# AmbaSat-1v1-01-NO-solar.net
KiCad netlist of a schematic drawn in EAGLE
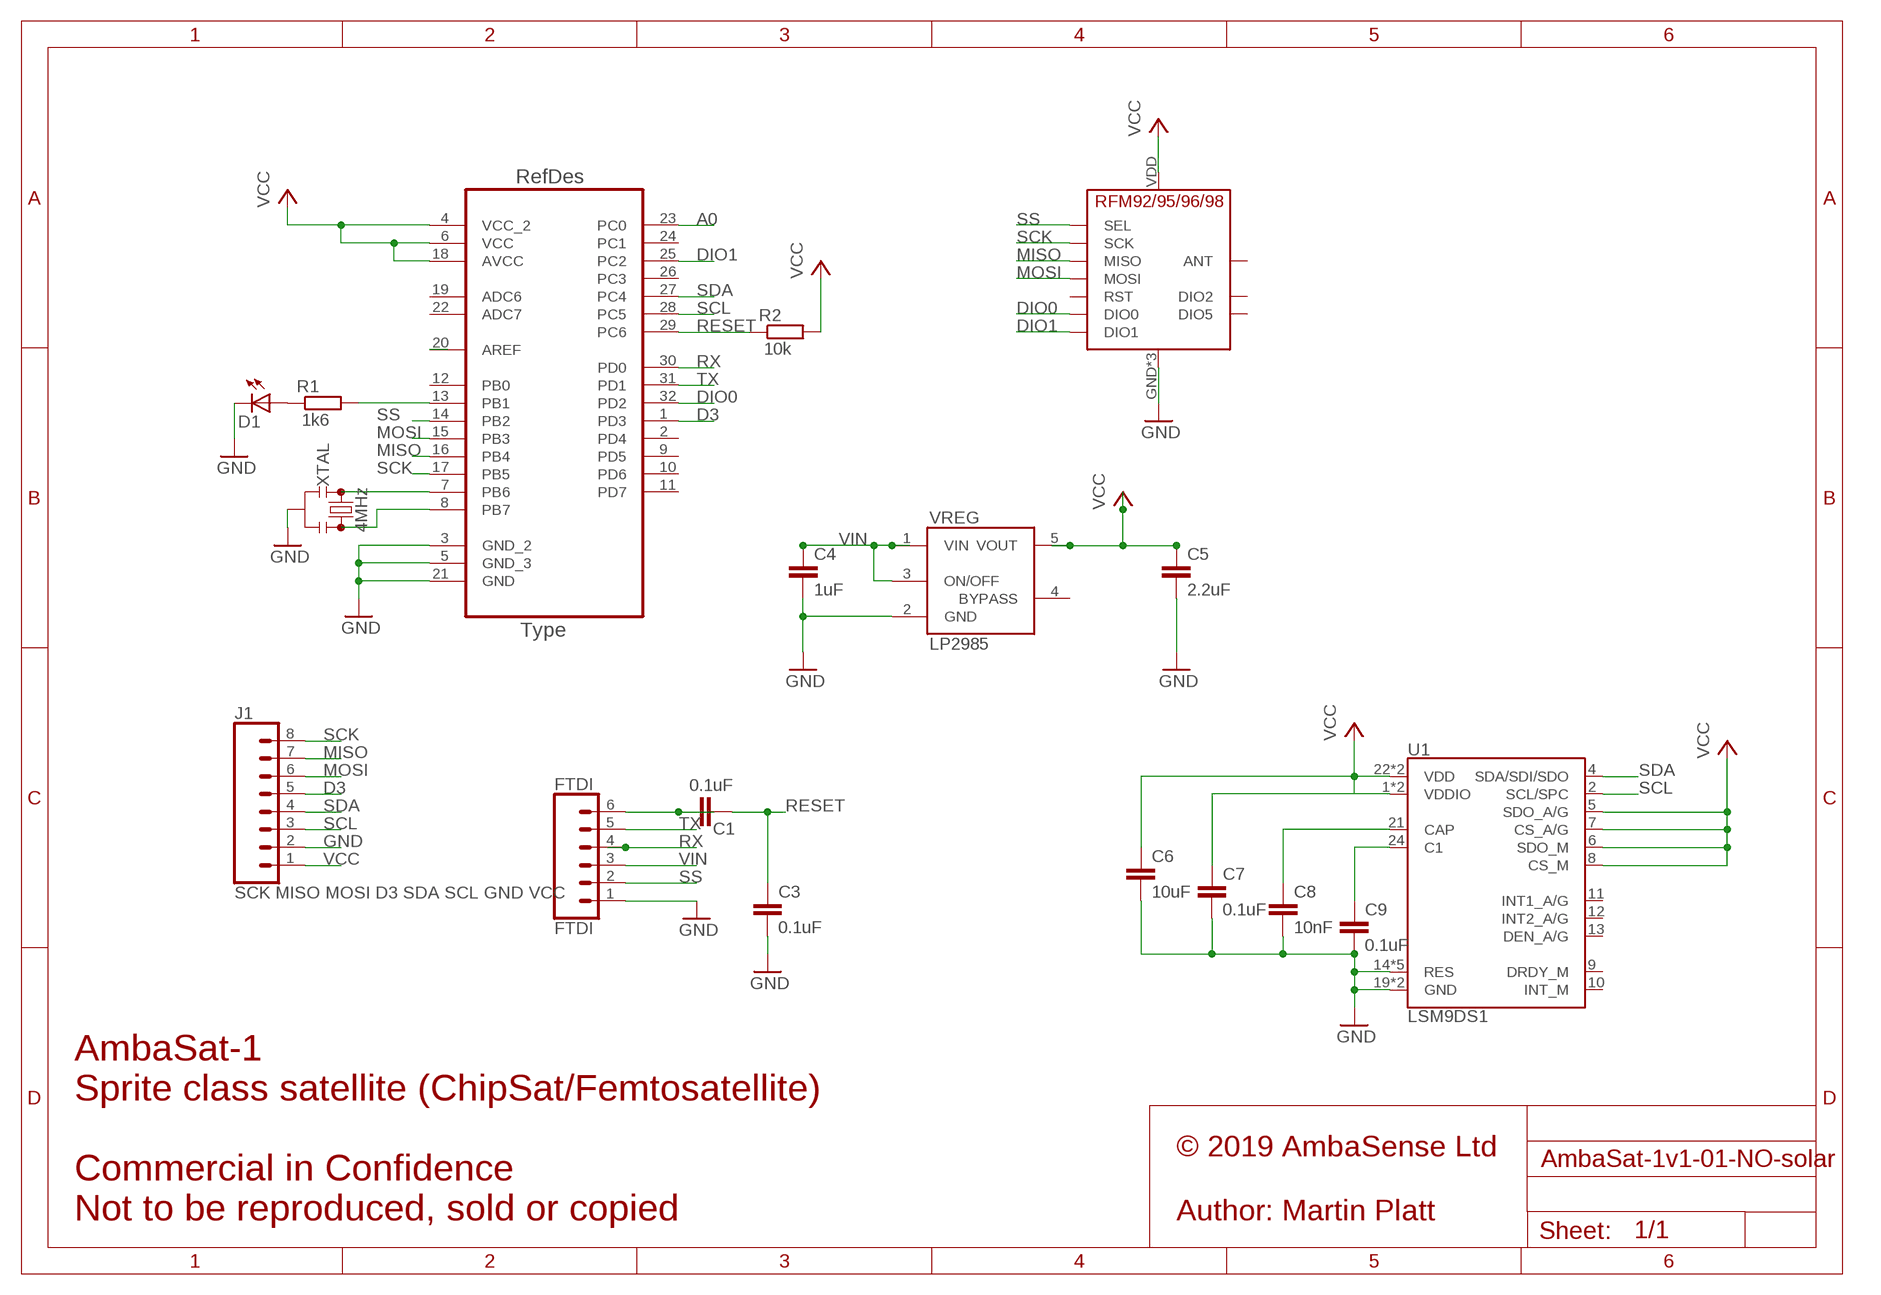
[diagram p0: schematic, sheet 1]

(export (version "E")
  (design (tool "Eeschema 10.0.6"))
  (components
    (comp (ref "ATMEGA328P-AU")
      (value "ATMEGA328P-AU")
      (footprint "eagle-import:QFP80P900X900X120-32N")
      (libsource (lib "eagle-import") (part "ATMEGA328P-AU"))
    )
    (comp (ref "C1")
      (value "0.1uF")
      (footprint "eagle-import:C0805K")
      (libsource (lib "eagle-import") (part "C-EUC0805K"))
    )
    (comp (ref "C3")
      (value "0.1uF")
      (footprint "eagle-import:C0805K")
      (libsource (lib "eagle-import") (part "C-EUC0805K"))
    )
    (comp (ref "C4")
      (value "1uF")
      (footprint "eagle-import:C0805K")
      (libsource (lib "eagle-import") (part "C-EUC0805K"))
    )
    (comp (ref "C5")
      (value "2.2uF")
      (footprint "eagle-import:C0805K")
      (libsource (lib "eagle-import") (part "C-EUC0805K"))
    )
    (comp (ref "C6")
      (value "10uF")
      (footprint "eagle-import:C0805K")
      (libsource (lib "eagle-import") (part "C-EUC0805K"))
    )
    (comp (ref "C7")
      (value "0.1uF")
      (footprint "eagle-import:C0805K")
      (libsource (lib "eagle-import") (part "C-EUC0805K"))
    )
    (comp (ref "C8")
      (value "10nF")
      (footprint "eagle-import:C0805K")
      (libsource (lib "eagle-import") (part "C-EUC0805K"))
    )
    (comp (ref "C9")
      (value "0.1uF")
      (footprint "eagle-import:C0805K")
      (libsource (lib "eagle-import") (part "C-EUC0805K"))
    )
    (comp (ref "D1")
      (value "LEDCHIP-LED0805")
      (footprint "eagle-import:CHIP-LED0805")
      (libsource (lib "eagle-import") (part "LEDCHIP-LED0805"))
    )
    (comp (ref "FTDI")
      (value "FTDI")
      (footprint "eagle-import:1X06_LONGPADS")
      (libsource (lib "eagle-import") (part "CONN_06LONGPADS"))
    )
    (comp (ref "J1")
      (value "SCK MISO MOSI D3 SDA SCL GND VCC")
      (footprint "eagle-import:1X08_LONGPADS")
      (libsource (lib "eagle-import") (part "CONN_08LONGPADS"))
    )
    (comp (ref "R1")
      (value "1k6")
      (footprint "eagle-import:M0805")
      (libsource (lib "eagle-import") (part "R-EU_M0805"))
    )
    (comp (ref "R2")
      (value "10k")
      (footprint "eagle-import:M0805")
      (libsource (lib "eagle-import") (part "R-EU_M0805"))
    )
    (comp (ref "RFM95")
      (value "RFM95")
      (footprint "eagle-import:RFM95")
      (libsource (lib "eagle-import") (part "RFM95"))
    )
    (comp (ref "U1")
      (value "LSM9DS1")
      (footprint "eagle-import:LGA24-8X4")
      (libsource (lib "eagle-import") (part "LSM9DS1"))
    )
    (comp (ref "VREG")
      (value "LP2985AIM5-3.3")
      (footprint "eagle-import:SOT25")
      (libsource (lib "eagle-import") (part "LP2985AIM5-3.3"))
    )
    (comp (ref "XTAL")
      (value "4MHz")
      (footprint "eagle-import:RESONATOR-SMD-4.5X2.0")
      (libsource (lib "eagle-import") (part "RESONATOR-4MHZSMD-4.5X2"))
    )
  )
  (nets
    (net (code "1") (name "/A0") (class "Default")
      (node (ref "ATMEGA328P-AU") (pin "23") (pinfunction "PC0_23") (pintype "bidirectional"))
    )
    (net (code "2") (name "/BYPASS") (class "Default")
      (node (ref "VREG") (pin "4") (pinfunction "BYPASS_4") (pintype "power_in"))
    )
    (net (code "3") (name "/D3") (class "Default")
      (node (ref "ATMEGA328P-AU") (pin "1") (pinfunction "PD3_1") (pintype "bidirectional"))
      (node (ref "J1") (pin "5") (pinfunction "5_5") (pintype "passive"))
    )
    (net (code "4") (name "/DIO0") (class "Default")
      (node (ref "ATMEGA328P-AU") (pin "32") (pinfunction "PD2_32") (pintype "bidirectional"))
      (node (ref "RFM95") (pin "DIO0") (pinfunction "DIO0_DIO0") (pintype "open_collector"))
    )
    (net (code "5") (name "/DIO1") (class "Default")
      (node (ref "ATMEGA328P-AU") (pin "25") (pinfunction "PC2_25") (pintype "bidirectional"))
      (node (ref "RFM95") (pin "DIO1") (pinfunction "DIO1_DIO1") (pintype "open_collector"))
    )
    (net (code "6") (name "/MISO") (class "Default")
      (node (ref "ATMEGA328P-AU") (pin "16") (pinfunction "PB4_16") (pintype "bidirectional"))
      (node (ref "J1") (pin "7") (pinfunction "7_7") (pintype "passive"))
      (node (ref "RFM95") (pin "MISO") (pinfunction "MISO_MISO") (pintype "input"))
    )
    (net (code "7") (name "/MOSI") (class "Default")
      (node (ref "ATMEGA328P-AU") (pin "15") (pinfunction "PB3_15") (pintype "bidirectional"))
      (node (ref "J1") (pin "6") (pinfunction "6_6") (pintype "passive"))
      (node (ref "RFM95") (pin "MOSI") (pinfunction "MOSI_MOSI") (pintype "output"))
    )
    (net (code "8") (name "/RESET") (class "Default")
      (node (ref "ATMEGA328P-AU") (pin "29") (pinfunction "PC6_29") (pintype "bidirectional"))
      (node (ref "C1") (pin "1") (pinfunction "1_1") (pintype "passive"))
      (node (ref "C3") (pin "1") (pinfunction "1_1") (pintype "passive"))
      (node (ref "R2") (pin "1") (pinfunction "1_1") (pintype "passive"))
    )
    (net (code "9") (name "/RX") (class "Default")
      (node (ref "ATMEGA328P-AU") (pin "30") (pinfunction "PD0_30") (pintype "bidirectional"))
      (node (ref "FTDI") (pin "4") (pinfunction "4_4") (pintype "passive"))
    )
    (net (code "10") (name "/SCK") (class "Default")
      (node (ref "ATMEGA328P-AU") (pin "17") (pinfunction "PB5_17") (pintype "bidirectional"))
      (node (ref "J1") (pin "8") (pinfunction "8_8") (pintype "passive"))
      (node (ref "RFM95") (pin "SCK") (pinfunction "SCK_SCK") (pintype "input"))
    )
    (net (code "11") (name "/SCL") (class "Default")
      (node (ref "ATMEGA328P-AU") (pin "28") (pinfunction "PC5_28") (pintype "bidirectional"))
      (node (ref "J1") (pin "3") (pinfunction "3_3") (pintype "passive"))
      (node (ref "U1") (pin "2") (pinfunction "SCL/SPC_2") (pintype "bidirectional"))
    )
    (net (code "12") (name "/SDA") (class "Default")
      (node (ref "ATMEGA328P-AU") (pin "27") (pinfunction "PC4_27") (pintype "bidirectional"))
      (node (ref "J1") (pin "4") (pinfunction "4_4") (pintype "passive"))
      (node (ref "U1") (pin "4") (pinfunction "SDA/SDI/SDO_4") (pintype "bidirectional"))
    )
    (net (code "13") (name "/SS") (class "Default")
      (node (ref "ATMEGA328P-AU") (pin "14") (pinfunction "PB2_14") (pintype "bidirectional"))
      (node (ref "FTDI") (pin "2") (pinfunction "2_2") (pintype "passive"))
      (node (ref "RFM95") (pin "NSS") (pinfunction "SEL_NSS") (pintype "input"))
    )
    (net (code "14") (name "/TX") (class "Default")
      (node (ref "ATMEGA328P-AU") (pin "31") (pinfunction "PD1_31") (pintype "bidirectional"))
      (node (ref "FTDI") (pin "5") (pinfunction "5_5") (pintype "passive"))
    )
    (net (code "15") (name "/VIN") (class "Default")
      (node (ref "C4") (pin "1") (pinfunction "1_1") (pintype "passive"))
      (node (ref "FTDI") (pin "3") (pinfunction "3_3") (pintype "passive"))
      (node (ref "VREG") (pin "1") (pinfunction "VIN_1") (pintype "power_in"))
      (node (ref "VREG") (pin "3") (pinfunction "ON/OFF_3") (pintype "input"))
    )
    (net (code "16") (name "GND") (class "Default")
      (node (ref "ATMEGA328P-AU") (pin "21") (pinfunction "GND_21") (pintype "passive"))
      (node (ref "ATMEGA328P-AU") (pin "3") (pinfunction "GND_2_3") (pintype "passive"))
      (node (ref "ATMEGA328P-AU") (pin "5") (pinfunction "GND_3_5") (pintype "passive"))
      (node (ref "C3") (pin "2") (pinfunction "2_2") (pintype "passive"))
      (node (ref "C4") (pin "2") (pinfunction "2_2") (pintype "passive"))
      (node (ref "C5") (pin "2") (pinfunction "2_2") (pintype "passive"))
      (node (ref "C6") (pin "2") (pinfunction "2_2") (pintype "passive"))
      (node (ref "C7") (pin "2") (pinfunction "2_2") (pintype "passive"))
      (node (ref "C8") (pin "2") (pinfunction "2_2") (pintype "passive"))
      (node (ref "C9") (pin "2") (pinfunction "2_2") (pintype "passive"))
      (node (ref "D1") (pin "C") (pinfunction "C_C") (pintype "passive"))
      (node (ref "FTDI") (pin "1") (pinfunction "1_1") (pintype "passive"))
      (node (ref "J1") (pin "2") (pinfunction "2_2") (pintype "passive"))
      (node (ref "RFM95") (pin "GND") (pinfunction "GND_GND") (pintype "power_in"))
      (node (ref "RFM95") (pin "GND1") (pinfunction "GND_GND1") (pintype "power_in"))
      (node (ref "RFM95") (pin "GND2") (pinfunction "GND_GND2") (pintype "power_in"))
      (node (ref "U1") (pin "14") (pinfunction "RES_14") (pintype "bidirectional"))
      (node (ref "U1") (pin "15") (pinfunction "RES_15") (pintype "bidirectional"))
      (node (ref "U1") (pin "16") (pinfunction "RES_16") (pintype "bidirectional"))
      (node (ref "U1") (pin "17") (pinfunction "RES_17") (pintype "bidirectional"))
      (node (ref "U1") (pin "18") (pinfunction "RES_18") (pintype "bidirectional"))
      (node (ref "U1") (pin "19") (pinfunction "GND_19") (pintype "bidirectional"))
      (node (ref "U1") (pin "20") (pinfunction "GND_20") (pintype "bidirectional"))
      (node (ref "VREG") (pin "2") (pinfunction "GND_2") (pintype "power_in"))
      (node (ref "XTAL") (pin "2") (pinfunction "2_2") (pintype "passive"))
    )
    (net (code "17") (name "Net-(ATMEGA328P-AU-PB1)") (class "Default")
      (node (ref "ATMEGA328P-AU") (pin "13") (pinfunction "PB1_13") (pintype "bidirectional"))
      (node (ref "R1") (pin "2") (pinfunction "2_2") (pintype "passive"))
    )
    (net (code "18") (name "Net-(ATMEGA328P-AU-PB6)") (class "Default")
      (node (ref "ATMEGA328P-AU") (pin "7") (pinfunction "PB6_7") (pintype "bidirectional"))
      (node (ref "XTAL") (pin "1") (pinfunction "1_1") (pintype "passive"))
    )
    (net (code "19") (name "Net-(ATMEGA328P-AU-PB7)") (class "Default")
      (node (ref "ATMEGA328P-AU") (pin "8") (pinfunction "PB7_8") (pintype "bidirectional"))
      (node (ref "XTAL") (pin "3") (pinfunction "3_3") (pintype "passive"))
    )
    (net (code "20") (name "Net-(C1-Pad2)") (class "Default")
      (node (ref "C1") (pin "2") (pinfunction "2_2") (pintype "passive"))
      (node (ref "FTDI") (pin "6") (pinfunction "6_6") (pintype "passive"))
    )
    (net (code "21") (name "Net-(D1-PadA)") (class "Default")
      (node (ref "D1") (pin "A") (pinfunction "A_A") (pintype "passive"))
      (node (ref "R1") (pin "1") (pinfunction "1_1") (pintype "passive"))
    )
    (net (code "22") (name "Net-(U1-C1)") (class "Default")
      (node (ref "C9") (pin "1") (pinfunction "1_1") (pintype "passive"))
      (node (ref "U1") (pin "24") (pinfunction "C1_24") (pintype "bidirectional"))
    )
    (net (code "23") (name "Net-(U1-CAP)") (class "Default")
      (node (ref "C8") (pin "1") (pinfunction "1_1") (pintype "passive"))
      (node (ref "U1") (pin "21") (pinfunction "CAP_21") (pintype "bidirectional"))
    )
    (net (code "24") (name "VCC") (class "Default")
      (node (ref "ATMEGA328P-AU") (pin "18") (pinfunction "AVCC_18") (pintype "power_in"))
      (node (ref "ATMEGA328P-AU") (pin "4") (pinfunction "VCC_2_4") (pintype "power_in"))
      (node (ref "ATMEGA328P-AU") (pin "6") (pinfunction "VCC_6") (pintype "power_in"))
      (node (ref "C5") (pin "1") (pinfunction "1_1") (pintype "passive"))
      (node (ref "C6") (pin "1") (pinfunction "1_1") (pintype "passive"))
      (node (ref "C7") (pin "1") (pinfunction "1_1") (pintype "passive"))
      (node (ref "J1") (pin "1") (pinfunction "1_1") (pintype "passive"))
      (node (ref "R2") (pin "2") (pinfunction "2_2") (pintype "passive"))
      (node (ref "RFM95") (pin "VDD") (pinfunction "VCC_VDD") (pintype "power_in"))
      (node (ref "U1") (pin "1") (pinfunction "VDDIO_1") (pintype "bidirectional"))
      (node (ref "U1") (pin "22") (pinfunction "VDD_22") (pintype "bidirectional"))
      (node (ref "U1") (pin "23") (pinfunction "VDD_23") (pintype "bidirectional"))
      (node (ref "U1") (pin "3") (pinfunction "VDDIO_3") (pintype "bidirectional"))
      (node (ref "U1") (pin "5") (pinfunction "SDO_A/G_5") (pintype "bidirectional"))
      (node (ref "U1") (pin "6") (pinfunction "SDO_M_6") (pintype "bidirectional"))
      (node (ref "U1") (pin "7") (pinfunction "CS_A/G_7") (pintype "bidirectional"))
      (node (ref "U1") (pin "8") (pinfunction "CS_M_8") (pintype "bidirectional"))
      (node (ref "VREG") (pin "5") (pinfunction "VOUT_5") (pintype "power_in"))
    )
    (net (code "25") (name "unconnected-(ATMEGA328P-AU-ADC6-Pad19)") (class "Default")
      (node (ref "ATMEGA328P-AU") (pin "19") (pinfunction "ADC6_19") (pintype "input"))
    )
    (net (code "26") (name "unconnected-(ATMEGA328P-AU-ADC7-Pad22)") (class "Default")
      (node (ref "ATMEGA328P-AU") (pin "22") (pinfunction "ADC7_22") (pintype "input"))
    )
    (net (code "27") (name "unconnected-(ATMEGA328P-AU-AREF-Pad20)") (class "Default")
      (node (ref "ATMEGA328P-AU") (pin "20") (pinfunction "AREF_20") (pintype "input"))
    )
    (net (code "28") (name "unconnected-(ATMEGA328P-AU-PB0-Pad12)") (class "Default")
      (node (ref "ATMEGA328P-AU") (pin "12") (pinfunction "PB0_12") (pintype "bidirectional"))
    )
    (net (code "29") (name "unconnected-(ATMEGA328P-AU-PC1-Pad24)") (class "Default")
      (node (ref "ATMEGA328P-AU") (pin "24") (pinfunction "PC1_24") (pintype "bidirectional"))
    )
    (net (code "30") (name "unconnected-(ATMEGA328P-AU-PC3-Pad26)") (class "Default")
      (node (ref "ATMEGA328P-AU") (pin "26") (pinfunction "PC3_26") (pintype "bidirectional"))
    )
    (net (code "31") (name "unconnected-(ATMEGA328P-AU-PD4-Pad2)") (class "Default")
      (node (ref "ATMEGA328P-AU") (pin "2") (pinfunction "PD4_2") (pintype "bidirectional"))
    )
    (net (code "32") (name "unconnected-(ATMEGA328P-AU-PD5-Pad9)") (class "Default")
      (node (ref "ATMEGA328P-AU") (pin "9") (pinfunction "PD5_9") (pintype "bidirectional"))
    )
    (net (code "33") (name "unconnected-(ATMEGA328P-AU-PD6-Pad10)") (class "Default")
      (node (ref "ATMEGA328P-AU") (pin "10") (pinfunction "PD6_10") (pintype "bidirectional"))
    )
    (net (code "34") (name "unconnected-(ATMEGA328P-AU-PD7-Pad11)") (class "Default")
      (node (ref "ATMEGA328P-AU") (pin "11") (pinfunction "PD7_11") (pintype "bidirectional"))
    )
    (net (code "35") (name "unconnected-(RFM95-PadANT)") (class "Default")
      (node (ref "RFM95") (pin "ANT") (pinfunction "ANT_ANT") (pintype "passive"))
    )
    (net (code "36") (name "unconnected-(RFM95-PadDIO2)") (class "Default")
      (node (ref "RFM95") (pin "DIO2") (pinfunction "DIO2_DIO2") (pintype "open_collector"))
    )
    (net (code "37") (name "unconnected-(RFM95-PadDIO5)") (class "Default")
      (node (ref "RFM95") (pin "DIO5") (pinfunction "DIO5_DIO5") (pintype "open_collector"))
    )
    (net (code "38") (name "unconnected-(RFM95-PadRST)") (class "Default")
      (node (ref "RFM95") (pin "RST") (pinfunction "RST_RST") (pintype "open_collector"))
    )
    (net (code "39") (name "unconnected-(U1-DEN_A{slash}G-Pad13)") (class "Default")
      (node (ref "U1") (pin "13") (pinfunction "DEN_A/G_13") (pintype "bidirectional"))
    )
    (net (code "40") (name "unconnected-(U1-DRDY_M-Pad9)") (class "Default")
      (node (ref "U1") (pin "9") (pinfunction "DRDY_M_9") (pintype "bidirectional"))
    )
    (net (code "41") (name "unconnected-(U1-INT1_A{slash}G-Pad11)") (class "Default")
      (node (ref "U1") (pin "11") (pinfunction "INT1_A/G_11") (pintype "bidirectional"))
    )
    (net (code "42") (name "unconnected-(U1-INT2_A{slash}G-Pad12)") (class "Default")
      (node (ref "U1") (pin "12") (pinfunction "INT2_A/G_12") (pintype "bidirectional"))
    )
    (net (code "43") (name "unconnected-(U1-INT_M-Pad10)") (class "Default")
      (node (ref "U1") (pin "10") (pinfunction "INT_M_10") (pintype "bidirectional"))
    )
  )
)
